# 03a_POWER-DISCRETE.net
KiCad netlist of a schematic drawn in Altium Designer
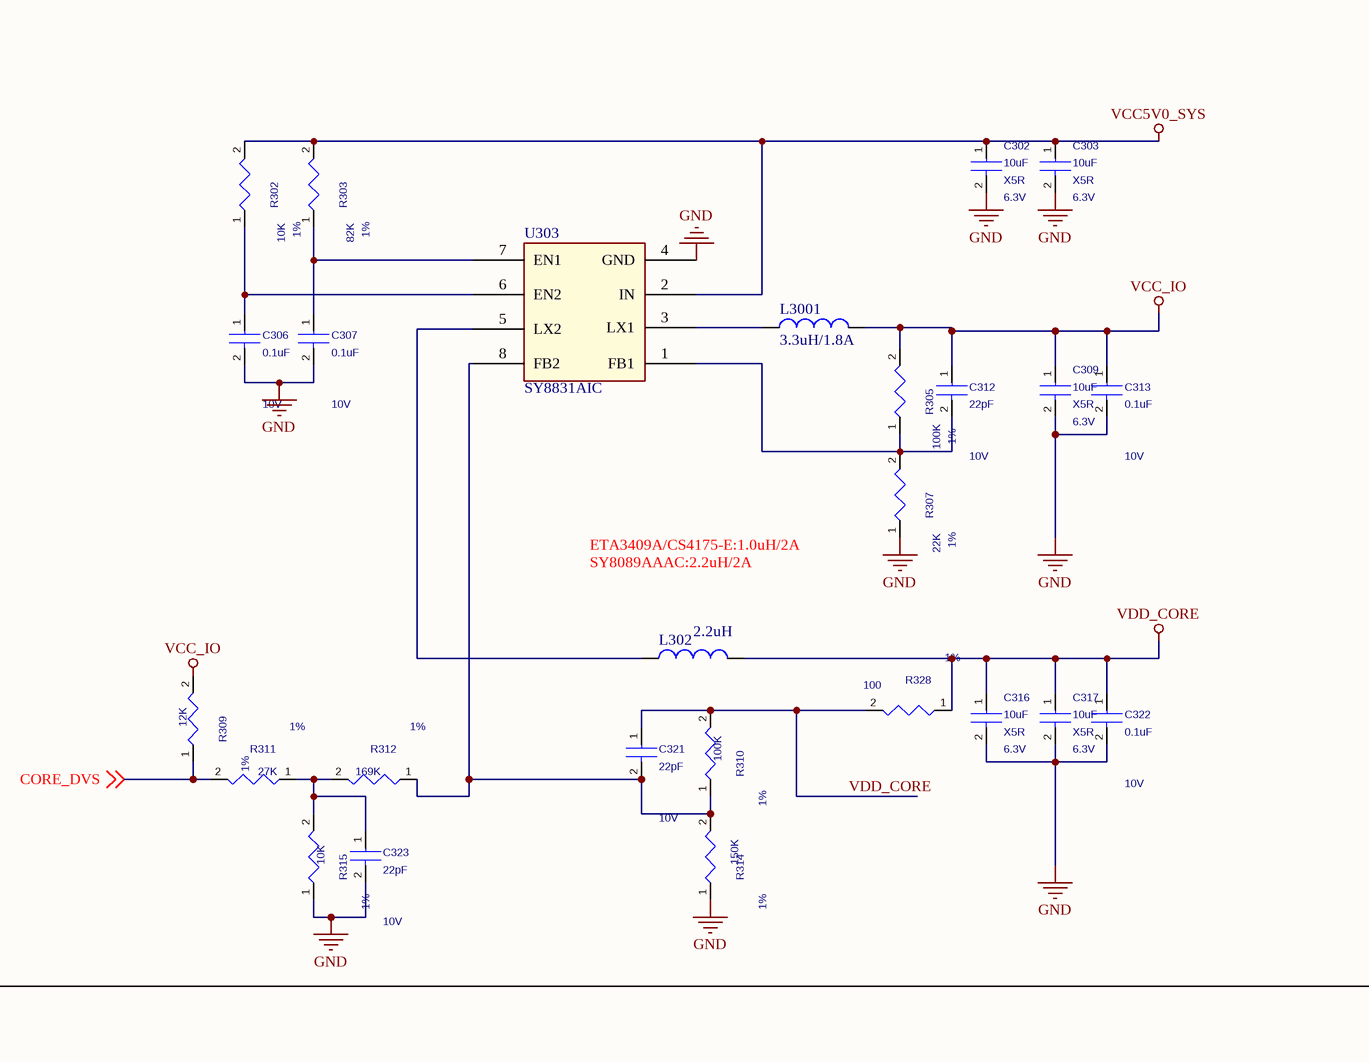
[diagram p0: 03a_POWER-DISCRETE.SchDoc, top left]
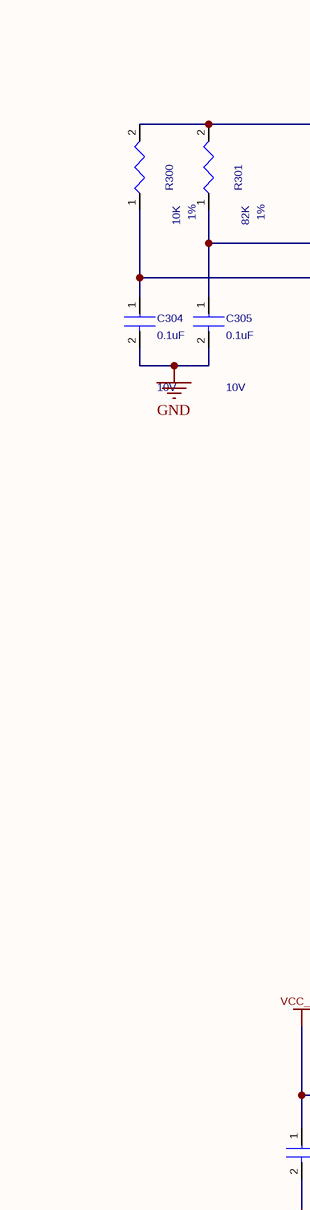
[diagram p1: 03a_POWER-DISCRETE.SchDoc, top middle]
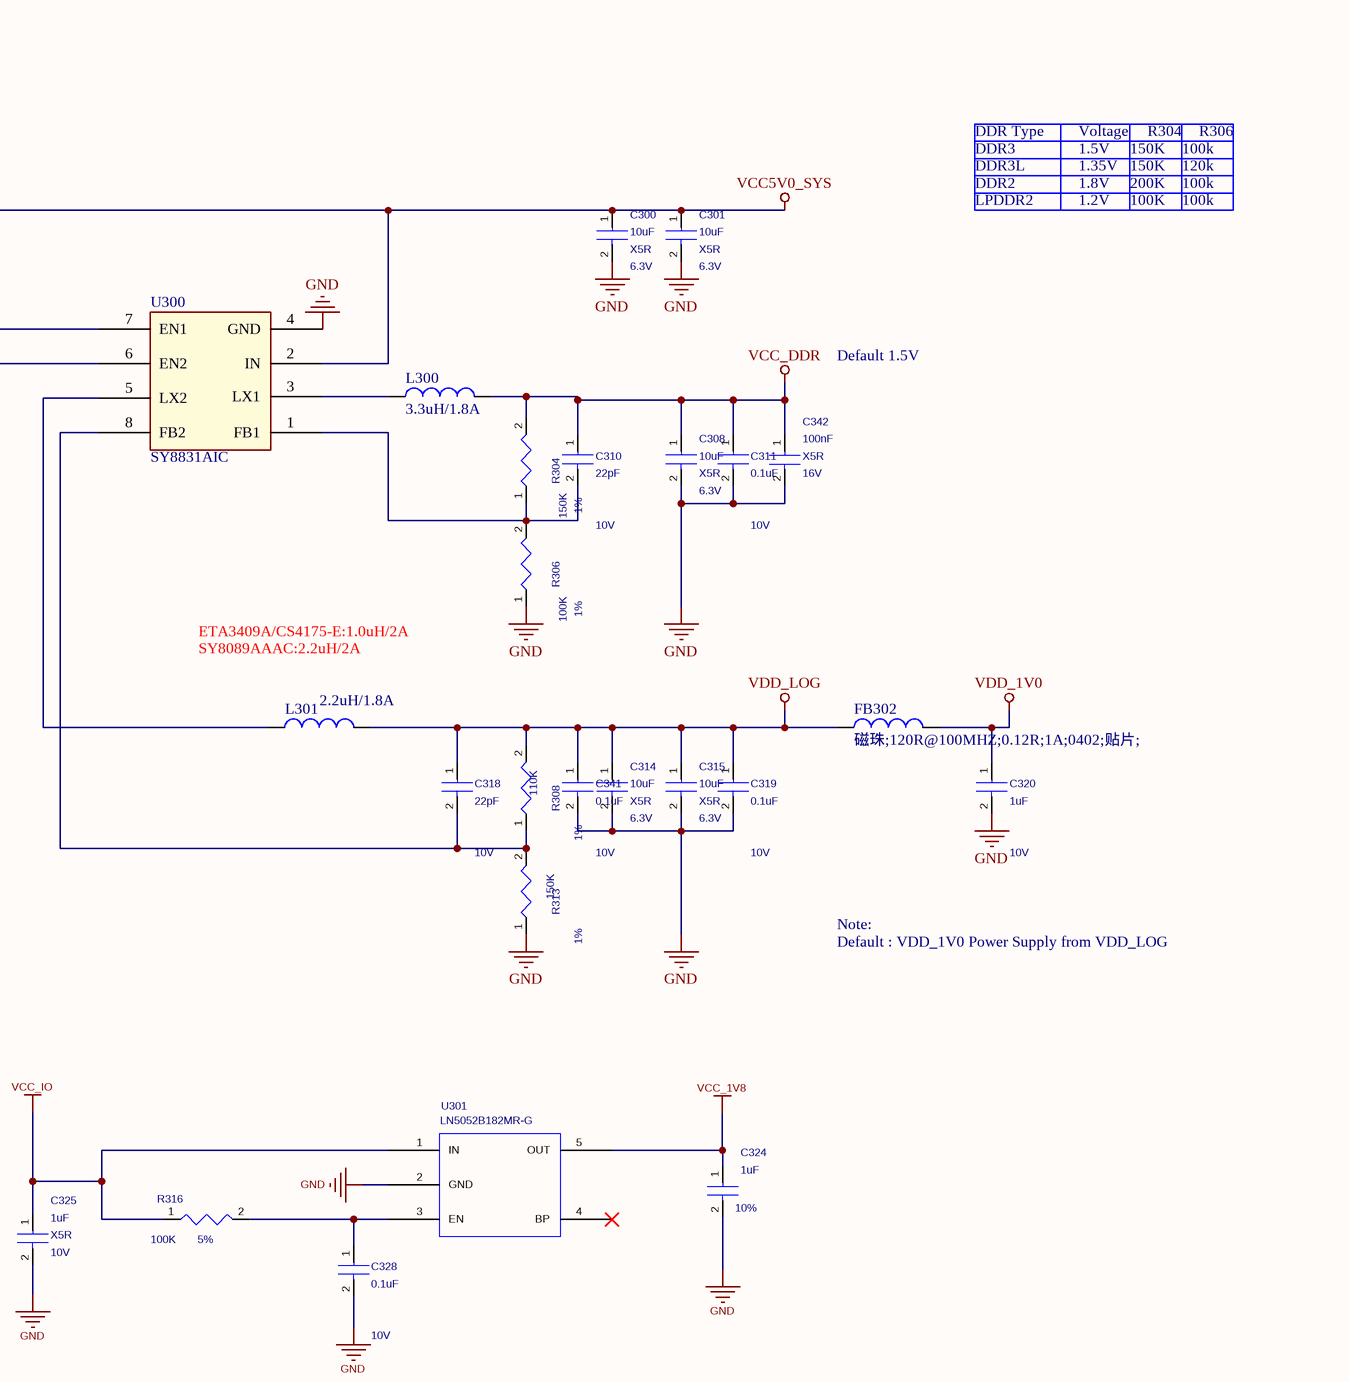
[diagram p2: 03a_POWER-DISCRETE.SchDoc, top right]
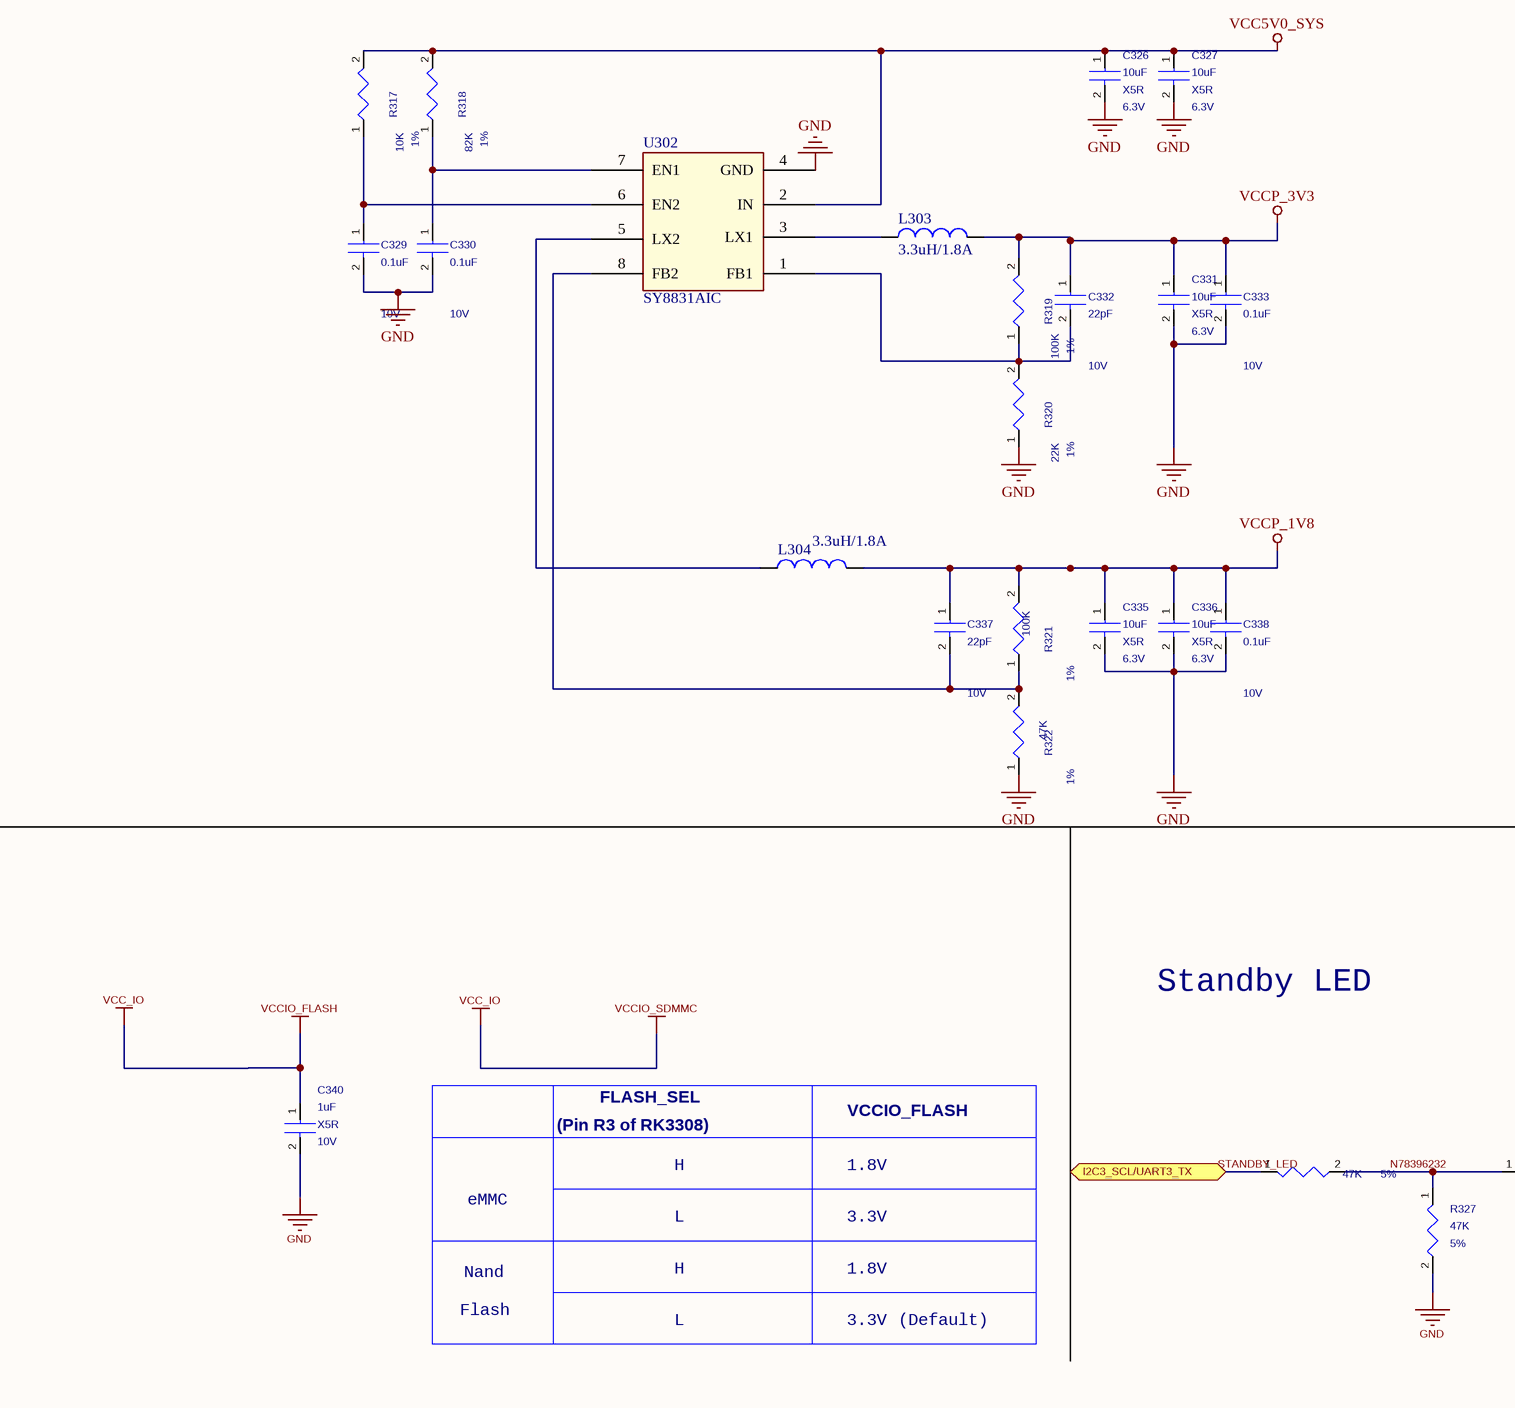
[diagram p3: 03a_POWER-DISCRETE.SchDoc, bottom left]
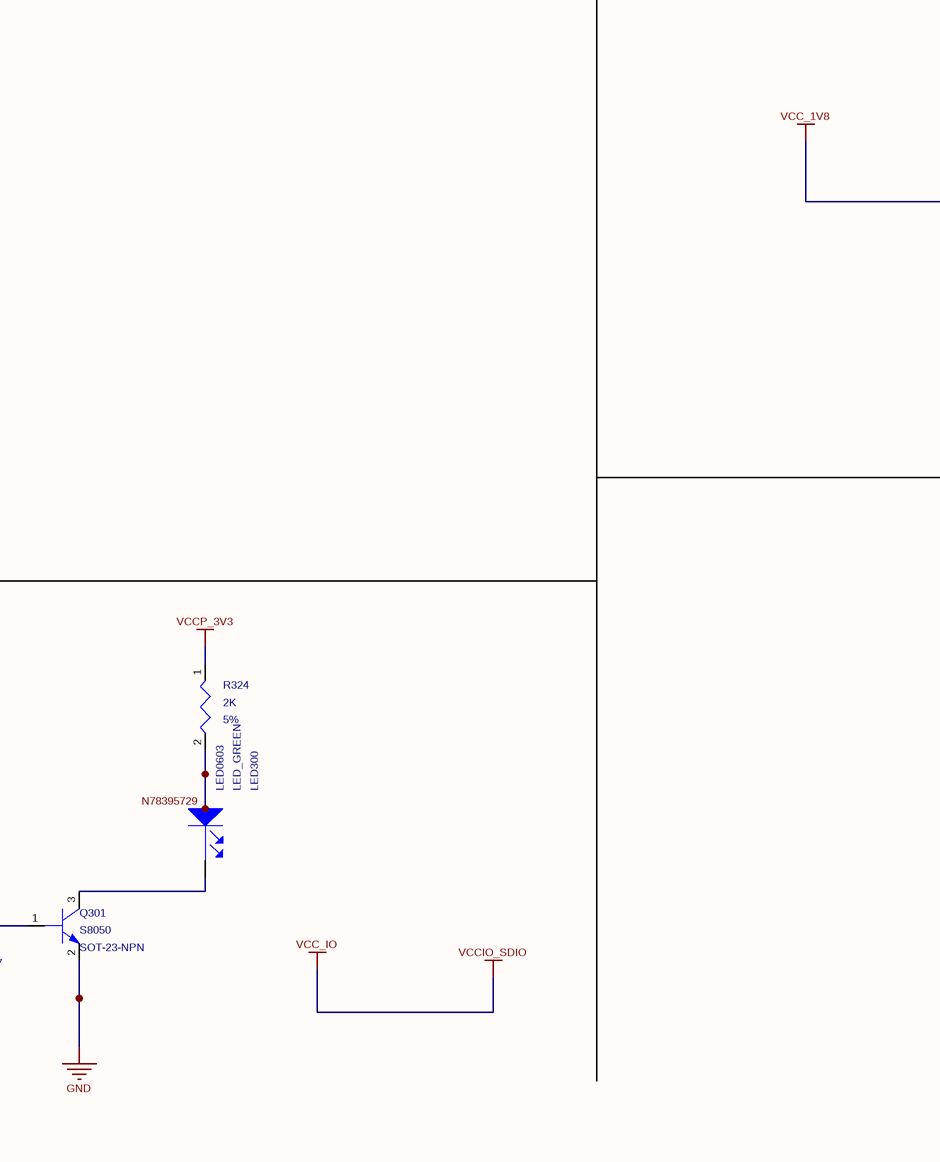
[diagram p4: 03a_POWER-DISCRETE.SchDoc, bottom middle]
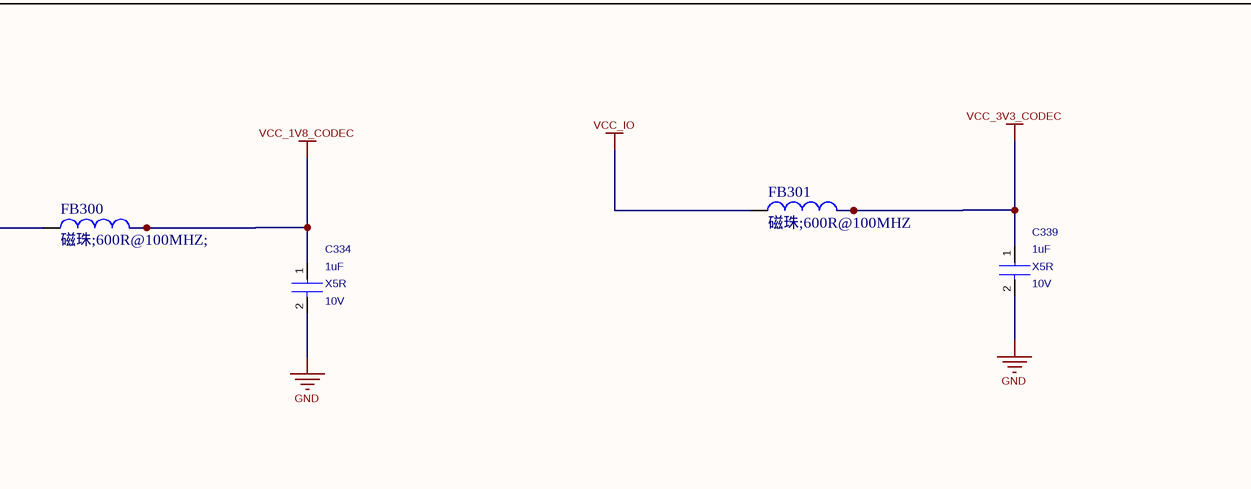
[diagram p5: 03a_POWER-DISCRETE.SchDoc, bottom right]

(export (version "E")
  (design (tool "Eeschema 10.0.6"))
  (components
    (comp (ref "C300")
      (value "10uF")
      (footprint "C0603")
      (description "cap,10.00uF,+/-10%,6.3V,X5R,C0603")
      (fields
        (field (name "DIELECTRIC") "X5R")
        (field (name "VOLTAGE") "6.3V")
        (field (name "TOLERANCE") "10%")
        (field (name "MANUFACTURER") "TDK")
      )
      (libsource (lib "*") (part "CAP_NP_2"))
    )
    (comp (ref "C301")
      (value "10uF")
      (footprint "C0603")
      (description "cap,10.00uF,+/-10%,6.3V,X5R,C0603")
      (fields
        (field (name "DIELECTRIC") "X5R")
        (field (name "VOLTAGE") "6.3V")
        (field (name "TOLERANCE") "10%")
        (field (name "MANUFACTURER") "TDK")
      )
      (libsource (lib "*") (part "CAP_NP_2"))
    )
    (comp (ref "C302")
      (value "10uF")
      (footprint "C0603")
      (description "cap,10.00uF,+/-10%,6.3V,X5R,C0603")
      (fields
        (field (name "DIELECTRIC") "X5R")
        (field (name "VOLTAGE") "6.3V")
        (field (name "TOLERANCE") "10%")
        (field (name "MANUFACTURER") "TDK")
      )
      (libsource (lib "*") (part "CAP_NP_2"))
    )
    (comp (ref "C303")
      (value "10uF")
      (footprint "C0603")
      (description "cap,10.00uF,+/-10%,6.3V,X5R,C0603")
      (fields
        (field (name "DIELECTRIC") "X5R")
        (field (name "VOLTAGE") "6.3V")
        (field (name "TOLERANCE") "10%")
        (field (name "MANUFACTURER") "TDK")
      )
      (libsource (lib "*") (part "CAP_NP_2"))
    )
    (comp (ref "C304")
      (value "0.1uF")
      (footprint "C0402")
      (description "cap,0.1uF,+/-10%,10V,X5R,C0402")
      (fields
        (field (name "TOLERANCE") "10%")
        (field (name "MANUFACTURER") "TDK")
        (field (name "VOLTAGE") "10V")
      )
      (libsource (lib "*") (part "CAP_NP_2"))
    )
    (comp (ref "C305")
      (value "0.1uF")
      (footprint "C0402")
      (description "cap,0.1uF,+/-10%,10V,X5R,C0402")
      (fields
        (field (name "TOLERANCE") "10%")
        (field (name "MANUFACTURER") "TDK")
        (field (name "VOLTAGE") "10V")
      )
      (libsource (lib "*") (part "CAP_NP_2"))
    )
    (comp (ref "C306")
      (value "0.1uF")
      (footprint "C0402")
      (description "cap,0.1uF,+/-10%,10V,X5R,C0402")
      (fields
        (field (name "TOLERANCE") "10%")
        (field (name "MANUFACTURER") "TDK")
        (field (name "VOLTAGE") "10V")
      )
      (libsource (lib "*") (part "CAP_NP_2"))
    )
    (comp (ref "C307")
      (value "0.1uF")
      (footprint "C0402")
      (description "cap,0.1uF,+/-10%,10V,X5R,C0402")
      (fields
        (field (name "TOLERANCE") "10%")
        (field (name "MANUFACTURER") "TDK")
        (field (name "VOLTAGE") "10V")
      )
      (libsource (lib "*") (part "CAP_NP_2"))
    )
    (comp (ref "C308")
      (value "10uF")
      (footprint "C0603")
      (description "cap,10.00uF,+/-10%,6.3V,X5R,C0603")
      (fields
        (field (name "DIELECTRIC") "X5R")
        (field (name "VOLTAGE") "6.3V")
        (field (name "TOLERANCE") "10%")
        (field (name "MANUFACTURER") "TDK")
      )
      (libsource (lib "*") (part "CAP_NP_2"))
    )
    (comp (ref "C309")
      (value "10uF")
      (footprint "C0603")
      (description "cap,10.00uF,+/-10%,6.3V,X5R,C0603")
      (fields
        (field (name "DIELECTRIC") "X5R")
        (field (name "VOLTAGE") "6.3V")
        (field (name "TOLERANCE") "10%")
        (field (name "MANUFACTURER") "TDK")
      )
      (libsource (lib "*") (part "CAP_NP_2"))
    )
    (comp (ref "C310")
      (value "22pF")
      (footprint "C0402")
      (description "cap,22pF,+/-10%,10V,X5R,C0402")
      (fields
        (field (name "TOLERANCE") "10%")
        (field (name "MANUFACTURER") "TDK")
        (field (name "VOLTAGE") "10V")
      )
      (libsource (lib "*") (part "CAP_NP_2"))
    )
    (comp (ref "C311")
      (value "0.1uF")
      (footprint "C0402")
      (description "cap,0.1uF,+/-10%,10V,X5R,C0402")
      (fields
        (field (name "TOLERANCE") "10%")
        (field (name "MANUFACTURER") "TDK")
        (field (name "VOLTAGE") "10V")
      )
      (libsource (lib "*") (part "CAP_NP_2"))
    )
    (comp (ref "C312")
      (value "22pF")
      (footprint "C0402")
      (description "cap,22pF,+/-10%,10V,X5R,C0402")
      (fields
        (field (name "TOLERANCE") "10%")
        (field (name "MANUFACTURER") "TDK")
        (field (name "VOLTAGE") "10V")
      )
      (libsource (lib "*") (part "CAP_NP_2"))
    )
    (comp (ref "C313")
      (value "0.1uF")
      (footprint "C0402")
      (description "cap,0.1uF,+/-10%,10V,X5R,C0402")
      (fields
        (field (name "TOLERANCE") "10%")
        (field (name "MANUFACTURER") "TDK")
        (field (name "VOLTAGE") "10V")
      )
      (libsource (lib "*") (part "CAP_NP_2"))
    )
    (comp (ref "C314")
      (value "10uF")
      (footprint "C0603")
      (description "cap,10.00uF,+/-10%,6.3V,X5R,C0603")
      (fields
        (field (name "DIELECTRIC") "X5R")
        (field (name "VOLTAGE") "6.3V")
        (field (name "TOLERANCE") "10%")
        (field (name "MANUFACTURER") "TDK")
      )
      (libsource (lib "*") (part "CAP_NP_2"))
    )
    (comp (ref "C315")
      (value "10uF")
      (footprint "C0603")
      (description "cap,10.00uF,+/-10%,6.3V,X5R,C0603")
      (fields
        (field (name "DIELECTRIC") "X5R")
        (field (name "VOLTAGE") "6.3V")
        (field (name "TOLERANCE") "10%")
        (field (name "MANUFACTURER") "TDK")
      )
      (libsource (lib "*") (part "CAP_NP_2"))
    )
    (comp (ref "C316")
      (value "10uF")
      (footprint "C0603")
      (description "cap,10.00uF,+/-10%,6.3V,X5R,C0603")
      (fields
        (field (name "DIELECTRIC") "X5R")
        (field (name "VOLTAGE") "6.3V")
        (field (name "TOLERANCE") "10%")
        (field (name "MANUFACTURER") "TDK")
      )
      (libsource (lib "*") (part "CAP_NP_2"))
    )
    (comp (ref "C317")
      (value "10uF")
      (footprint "C0603")
      (description "cap,10.00uF,+/-10%,6.3V,X5R,C0603")
      (fields
        (field (name "DIELECTRIC") "X5R")
        (field (name "VOLTAGE") "6.3V")
        (field (name "TOLERANCE") "10%")
        (field (name "MANUFACTURER") "TDK")
      )
      (libsource (lib "*") (part "CAP_NP_2"))
    )
    (comp (ref "C318")
      (value "22pF")
      (footprint "C0402")
      (description "cap,22pF,+/-10%,10V,X5R,C0402")
      (fields
        (field (name "TOLERANCE") "10%")
        (field (name "MANUFACTURER") "TDK")
        (field (name "VOLTAGE") "10V")
      )
      (libsource (lib "*") (part "CAP_NP_2"))
    )
    (comp (ref "C319")
      (value "0.1uF")
      (footprint "C0402")
      (description "cap,0.1uF,+/-10%,10V,X5R,C0402")
      (fields
        (field (name "TOLERANCE") "10%")
        (field (name "MANUFACTURER") "TDK")
        (field (name "VOLTAGE") "10V")
      )
      (libsource (lib "*") (part "CAP_NP_2"))
    )
    (comp (ref "C320")
      (value "1uF")
      (footprint "C0402")
      (description "cap,1uF,+/-10%,10V,X5R,C0402")
      (fields
        (field (name "TOLERANCE") "10%")
        (field (name "MANUFACTURER") "TDK")
        (field (name "VOLTAGE") "10V")
      )
      (libsource (lib "*") (part "CAP_NP_2"))
    )
    (comp (ref "C321")
      (value "22pF")
      (footprint "C0402")
      (description "cap,22pF,+/-10%,10V,X5R,C0402")
      (fields
        (field (name "TOLERANCE") "10%")
        (field (name "MANUFACTURER") "TDK")
        (field (name "VOLTAGE") "10V")
      )
      (libsource (lib "*") (part "CAP_NP_2"))
    )
    (comp (ref "C322")
      (value "0.1uF")
      (footprint "C0402")
      (description "cap,0.1uF,+/-10%,10V,X5R,C0402")
      (fields
        (field (name "TOLERANCE") "10%")
        (field (name "MANUFACTURER") "TDK")
        (field (name "VOLTAGE") "10V")
      )
      (libsource (lib "*") (part "CAP_NP_2"))
    )
    (comp (ref "C323")
      (value "22pF")
      (footprint "C0402")
      (description "cap,22pF,+/-10%,10V,X5R,C0402")
      (fields
        (field (name "TOLERANCE") "10%")
        (field (name "MANUFACTURER") "TDK")
        (field (name "VOLTAGE") "10V")
      )
      (libsource (lib "*") (part "CAP_NP_2"))
    )
    (comp (ref "C324")
      (value "1uF")
      (footprint "C0402")
      (description "cap,1.00uF,+/-10%,10V,X5R,C0402")
      (fields
        (field (name "VOLTAGE") "10V")
        (field (name "MANUFACTURER") "TDK")
        (field (name "TOLERANCE") "10%")
      )
      (libsource (lib "*") (part "CAP_NP_2"))
    )
    (comp (ref "C325")
      (value "1uF")
      (footprint "C0402")
      (description "cap,1.00uF,+/-10%,10V,X5R,C0402")
      (fields
        (field (name "VOLTAGE") "10V")
        (field (name "DIELECTRIC") "X5R")
        (field (name "TOLERANCE") "10%")
        (field (name "MANUFACTURER") "TDK")
      )
      (libsource (lib "*") (part "CAP_NP_2"))
    )
    (comp (ref "C326")
      (value "10uF")
      (footprint "C0603")
      (description "cap,10.00uF,+/-10%,6.3V,X5R,C0603")
      (fields
        (field (name "DIELECTRIC") "X5R")
        (field (name "VOLTAGE") "6.3V")
        (field (name "TOLERANCE") "10%")
        (field (name "MANUFACTURER") "TDK")
      )
      (libsource (lib "*") (part "CAP_NP_2"))
    )
    (comp (ref "C327")
      (value "10uF")
      (footprint "C0603")
      (description "cap,10.00uF,+/-10%,6.3V,X5R,C0603")
      (fields
        (field (name "DIELECTRIC") "X5R")
        (field (name "VOLTAGE") "6.3V")
        (field (name "TOLERANCE") "10%")
        (field (name "MANUFACTURER") "TDK")
      )
      (libsource (lib "*") (part "CAP_NP_2"))
    )
    (comp (ref "C328")
      (value "0.1uF")
      (footprint "C0402")
      (description "cap,0.1uF,+/-10%,10V,X5R,C0402")
      (fields
        (field (name "TOLERANCE") "10%")
        (field (name "MANUFACTURER") "TDK")
        (field (name "VOLTAGE") "10V")
      )
      (libsource (lib "*") (part "CAP_NP_2"))
    )
    (comp (ref "C329")
      (value "0.1uF")
      (footprint "C0402")
      (description "cap,0.1uF,+/-10%,10V,X5R,C0402")
      (fields
        (field (name "TOLERANCE") "10%")
        (field (name "MANUFACTURER") "TDK")
        (field (name "VOLTAGE") "10V")
      )
      (libsource (lib "*") (part "CAP_NP_2"))
    )
    (comp (ref "C330")
      (value "0.1uF")
      (footprint "C0402")
      (description "cap,0.1uF,+/-10%,10V,X5R,C0402")
      (fields
        (field (name "TOLERANCE") "10%")
        (field (name "MANUFACTURER") "TDK")
        (field (name "VOLTAGE") "10V")
      )
      (libsource (lib "*") (part "CAP_NP_2"))
    )
    (comp (ref "C331")
      (value "10uF")
      (footprint "C0603")
      (description "cap,10.00uF,+/-10%,6.3V,X5R,C0603")
      (fields
        (field (name "DIELECTRIC") "X5R")
        (field (name "VOLTAGE") "6.3V")
        (field (name "TOLERANCE") "10%")
        (field (name "MANUFACTURER") "TDK")
      )
      (libsource (lib "*") (part "CAP_NP_2"))
    )
    (comp (ref "C332")
      (value "22pF")
      (footprint "C0402")
      (description "cap,22pF,+/-10%,10V,X5R,C0402")
      (fields
        (field (name "TOLERANCE") "10%")
        (field (name "MANUFACTURER") "TDK")
        (field (name "VOLTAGE") "10V")
      )
      (libsource (lib "*") (part "CAP_NP_2"))
    )
    (comp (ref "C333")
      (value "0.1uF")
      (footprint "C0402")
      (description "cap,0.1uF,+/-10%,10V,X5R,C0402")
      (fields
        (field (name "TOLERANCE") "10%")
        (field (name "MANUFACTURER") "TDK")
        (field (name "VOLTAGE") "10V")
      )
      (libsource (lib "*") (part "CAP_NP_2"))
    )
    (comp (ref "C334")
      (value "1uF")
      (footprint "C0402")
      (description "cap,1.00uF,+/-10%,10V,X5R,C0402")
      (fields
        (field (name "VOLTAGE") "10V")
        (field (name "MANUFACTURER") "TDK")
        (field (name "TOLERANCE") "10%")
        (field (name "DIELECTRIC") "X5R")
      )
      (libsource (lib "*") (part "CAP_NP_2"))
    )
    (comp (ref "C335")
      (value "10uF")
      (footprint "C0603")
      (description "cap,10.00uF,+/-10%,6.3V,X5R,C0603")
      (fields
        (field (name "DIELECTRIC") "X5R")
        (field (name "VOLTAGE") "6.3V")
        (field (name "TOLERANCE") "10%")
        (field (name "MANUFACTURER") "TDK")
      )
      (libsource (lib "*") (part "CAP_NP_2"))
    )
    (comp (ref "C336")
      (value "10uF")
      (footprint "C0603")
      (description "cap,10.00uF,+/-10%,6.3V,X5R,C0603")
      (fields
        (field (name "DIELECTRIC") "X5R")
        (field (name "VOLTAGE") "6.3V")
        (field (name "TOLERANCE") "10%")
        (field (name "MANUFACTURER") "TDK")
      )
      (libsource (lib "*") (part "CAP_NP_2"))
    )
    (comp (ref "C337")
      (value "22pF")
      (footprint "C0402")
      (description "cap,22pF,+/-10%,10V,X5R,C0402")
      (fields
        (field (name "TOLERANCE") "10%")
        (field (name "MANUFACTURER") "TDK")
        (field (name "VOLTAGE") "10V")
      )
      (libsource (lib "*") (part "CAP_NP_2"))
    )
    (comp (ref "C338")
      (value "0.1uF")
      (footprint "C0402")
      (description "cap,0.1uF,+/-10%,10V,X5R,C0402")
      (fields
        (field (name "TOLERANCE") "10%")
        (field (name "MANUFACTURER") "TDK")
        (field (name "VOLTAGE") "10V")
      )
      (libsource (lib "*") (part "CAP_NP_2"))
    )
    (comp (ref "C339")
      (value "1uF")
      (footprint "C0402")
      (description "cap,1.00uF,+/-10%,10V,X5R,C0402")
      (fields
        (field (name "VOLTAGE") "10V")
        (field (name "MANUFACTURER") "TDK")
        (field (name "TOLERANCE") "10%")
        (field (name "DIELECTRIC") "X5R")
      )
      (libsource (lib "*") (part "CAP_NP_2"))
    )
    (comp (ref "C340")
      (value "1uF")
      (footprint "C0402")
      (description "cap,1.00uF,+/-10%,10V,X5R,C0402")
      (fields
        (field (name "VOLTAGE") "10V")
        (field (name "MANUFACTURER") "TDK")
        (field (name "TOLERANCE") "10%")
        (field (name "DIELECTRIC") "X5R")
      )
      (libsource (lib "*") (part "CAP_NP_2"))
    )
    (comp (ref "C341")
      (value "0.1uF")
      (footprint "C0402")
      (description "cap,0.1uF,+/-10%,10V,X5R,C0402")
      (fields
        (field (name "TOLERANCE") "10%")
        (field (name "MANUFACTURER") "TDK")
        (field (name "VOLTAGE") "10V")
      )
      (libsource (lib "*") (part "CAP_NP_2"))
    )
    (comp (ref "C342")
      (value "100nF")
      (footprint "C0402")
      (description "cap,100.00nF,+/-10%,16V,X5R,C0402")
      (fields
        (field (name "VOLTAGE") "16V")
        (field (name "TOLERANCE") "10%")
        (field (name "MANUFACTURER") "TDK")
        (field (name "DIELECTRIC") "X5R")
      )
      (libsource (lib "*") (part "CAP_NP_2"))
    )
    (comp (ref "FB300")
      (value "磁珠;600R@100MHZ;")
      (footprint "L0402")
      (description "GZ0603D601TF")
      (libsource (lib "amenuo") (part "INDUCTOR"))
    )
    (comp (ref "FB301")
      (value "磁珠;600R@100MHZ")
      (footprint "L0402")
      (description "L0603-0欧姆-1A")
      (libsource (lib "amenuo") (part "INDUCTOR"))
    )
    (comp (ref "FB302")
      (value "磁珠;120R@100MHZ;0.12R;1A;0402;贴片;")
      (footprint "L0402")
      (description "PZ1005U121-1R0T")
      (libsource (lib "amenuo") (part "INDUCTOR"))
    )
    (comp (ref "L300")
      (value "3.3uH/1.8A")
      (footprint "IND2520")
      (description "SWPA252012S3R3MT")
      (libsource (lib "amenuo") (part "INDUCTOR"))
    )
    (comp (ref "L301")
      (value "2.2uH/1.8A")
      (footprint "IND2520")
      (description "SPH252012H2R2MT")
      (libsource (lib "amenuo") (part "INDUCTOR"))
    )
    (comp (ref "L302")
      (value "2.2uH")
      (footprint "IND2520")
      (description "SPH252012H2R2MT")
      (libsource (lib "amenuo") (part "INDUCTOR"))
    )
    (comp (ref "L303")
      (value "3.3uH/1.8A")
      (footprint "IND2520")
      (description "SWPA252012S3R3MT")
      (libsource (lib "amenuo") (part "INDUCTOR"))
    )
    (comp (ref "L304")
      (value "3.3uH/1.8A")
      (footprint "IND2520")
      (description "SWPA252012S3R3MT")
      (libsource (lib "amenuo") (part "INDUCTOR"))
    )
    (comp (ref "L3001")
      (value "3.3uH/1.8A")
      (footprint "IND2520")
      (description "SWPA252012S3R3MT")
      (libsource (lib "amenuo") (part "INDUCTOR"))
    )
    (comp (ref "LED300")
      (value "LED_GREEN")
      (footprint "LED0603")
      (description "贴片LED灯，0603，绿色")
      (fields (field (name "PCB DECAL") "LED0603") (field (name "Comment") "LED"))
      (libsource (lib "*") (part "LED"))
    )
    (comp (ref "Q301")
      (value "S8050")
      (footprint "SOT23")
      (description "S8050,SOT23")
      (fields
        (field (name "PCB DECAL") "SOT-23-NPN")
        (field (name "MANUFACTURER") "长电")
        (field (name "Comment") "NPN")
      )
      (libsource (lib "*") (part "NPN"))
    )
    (comp (ref "R300")
      (value "10K")
      (footprint "R0402")
      (description "?用厚膜电阻,10K,+/-1%,R0402,1/16W.")
      (fields
        (field (name "MANUFACTURER") "YAGEO")
        (field (name "TOLERANCE") "1%")
        (field (name "Comment") "RESISTOR")
      )
      (libsource (lib "*") (part "RESISTOR"))
    )
    (comp (ref "R301")
      (value "82K")
      (footprint "R0402")
      (description "?用厚膜电阻,82K,+/-1%,R0402,1/16W.")
      (fields
        (field (name "MANUFACTURER") "YAGEO")
        (field (name "TOLERANCE") "1%")
        (field (name "Comment") "RESISTOR")
      )
      (libsource (lib "*") (part "RESISTOR"))
    )
    (comp (ref "R302")
      (value "10K")
      (footprint "R0402")
      (description "?用厚膜电阻,10K,+/-1%,R0402,1/16W.")
      (fields
        (field (name "MANUFACTURER") "YAGEO")
        (field (name "TOLERANCE") "1%")
        (field (name "Comment") "RESISTOR")
      )
      (libsource (lib "*") (part "RESISTOR"))
    )
    (comp (ref "R303")
      (value "82K")
      (footprint "R0402")
      (description "?用厚膜电阻,82K,+/-1%,R0402,1/16W.")
      (fields
        (field (name "MANUFACTURER") "YAGEO")
        (field (name "TOLERANCE") "1%")
        (field (name "Comment") "RESISTOR")
      )
      (libsource (lib "*") (part "RESISTOR"))
    )
    (comp (ref "R304")
      (value "150K")
      (footprint "R0402")
      (description "?用厚膜电阻,150K,+/-1%,R0402,1/16W.")
      (fields
        (field (name "MANUFACTURER") "YAGEO")
        (field (name "TOLERANCE") "1%")
        (field (name "Comment") "RESISTOR")
      )
      (libsource (lib "*") (part "RESISTOR"))
    )
    (comp (ref "R305")
      (value "100K")
      (footprint "R0402")
      (description "?用厚膜电阻,100K,+/-1%,R0402,1/16W.")
      (fields
        (field (name "MANUFACTURER") "YAGEO")
        (field (name "TOLERANCE") "1%")
        (field (name "Comment") "RESISTOR")
      )
      (libsource (lib "*") (part "RESISTOR"))
    )
    (comp (ref "R306")
      (value "100K")
      (footprint "R0402")
      (description "?用厚膜电阻,100K,+/-1%,R0402,1/16W.")
      (fields
        (field (name "MANUFACTURER") "YAGEO")
        (field (name "TOLERANCE") "1%")
        (field (name "Comment") "RESISTOR")
      )
      (libsource (lib "*") (part "RESISTOR"))
    )
    (comp (ref "R307")
      (value "22K")
      (footprint "R0402")
      (description "?用厚膜电阻,22K,+/-1%,R0402,1/16W.")
      (fields
        (field (name "MANUFACTURER") "YAGEO")
        (field (name "TOLERANCE") "1%")
        (field (name "Comment") "RESISTOR")
      )
      (libsource (lib "*") (part "RESISTOR"))
    )
    (comp (ref "R308")
      (value "110K")
      (footprint "R0402")
      (description "?用厚膜电阻,110K,+/-1%,R0402,1/16W.")
      (fields
        (field (name "MANUFACTURER") "YAGEO")
        (field (name "TOLERANCE") "1%")
        (field (name "Comment") "RESISTOR")
      )
      (libsource (lib "*") (part "RESISTOR"))
    )
    (comp (ref "R309")
      (value "12K")
      (footprint "R0402")
      (description "?用厚膜电阻,12K,+/-1%,R0402,1/16W.")
      (fields
        (field (name "MANUFACTURER") "YAGEO")
        (field (name "TOLERANCE") "1%")
        (field (name "Comment") "RESISTOR")
      )
      (libsource (lib "*") (part "RESISTOR"))
    )
    (comp (ref "R310")
      (value "100K")
      (footprint "R0402")
      (description "?用厚膜电阻,100K,+/-1%,R0402,1/16W.")
      (fields
        (field (name "MANUFACTURER") "YAGEO")
        (field (name "TOLERANCE") "1%")
        (field (name "Comment") "RESISTOR")
      )
      (libsource (lib "*") (part "RESISTOR"))
    )
    (comp (ref "R311")
      (value "27K")
      (footprint "R0402")
      (description "?用厚膜电阻,27K,+/-1%,R0402,1/16W.")
      (fields
        (field (name "MANUFACTURER") "YAGEO")
        (field (name "TOLERANCE") "1%")
        (field (name "Comment") "RESISTOR")
      )
      (libsource (lib "*") (part "RESISTOR"))
    )
    (comp (ref "R312")
      (value "169K")
      (footprint "R0402")
      (description "?用厚膜电阻,169K,+/-1%,R0402,1/16W.")
      (fields
        (field (name "MANUFACTURER") "YAGEO")
        (field (name "TOLERANCE") "1%")
        (field (name "Comment") "RESISTOR")
      )
      (libsource (lib "*") (part "RESISTOR"))
    )
    (comp (ref "R313")
      (value "150K")
      (footprint "R0402")
      (description "?用厚膜电阻,150K,+/-1%,R0402,1/16W.")
      (fields
        (field (name "MANUFACTURER") "YAGEO")
        (field (name "TOLERANCE") "1%")
        (field (name "Comment") "RESISTOR")
      )
      (libsource (lib "*") (part "RESISTOR"))
    )
    (comp (ref "R314")
      (value "150K")
      (footprint "R0402")
      (description "?用厚膜电阻,150K,+/-1%,R0402,1/16W.")
      (fields
        (field (name "MANUFACTURER") "YAGEO")
        (field (name "TOLERANCE") "1%")
        (field (name "Comment") "RESISTOR")
      )
      (libsource (lib "*") (part "RESISTOR"))
    )
    (comp (ref "R315")
      (value "10K")
      (footprint "R0402")
      (description "?用厚膜电阻,10K,+/-1%,R0402,1/16W.")
      (fields
        (field (name "MANUFACTURER") "YAGEO")
        (field (name "TOLERANCE") "1%")
        (field (name "Comment") "RESISTOR")
      )
      (libsource (lib "*") (part "RESISTOR"))
    )
    (comp (ref "R316")
      (value "100K")
      (footprint "R0402")
      (description "?用厚膜电阻,100K,+/-5%,R0402,1/16W.")
      (fields
        (field (name "TOLERANCE") "5%")
        (field (name "MANUFACTURER") "YAGEO")
        (field (name "Comment") "RESISTOR")
      )
      (libsource (lib "*") (part "RESISTOR"))
    )
    (comp (ref "R317")
      (value "10K")
      (footprint "R0402")
      (description "?用厚膜电阻,10K,+/-1%,R0402,1/16W.")
      (fields
        (field (name "MANUFACTURER") "YAGEO")
        (field (name "TOLERANCE") "1%")
        (field (name "Comment") "RESISTOR")
      )
      (libsource (lib "*") (part "RESISTOR"))
    )
    (comp (ref "R318")
      (value "82K")
      (footprint "R0402")
      (description "?用厚膜电阻,82K,+/-1%,R0402,1/16W.")
      (fields
        (field (name "MANUFACTURER") "YAGEO")
        (field (name "TOLERANCE") "1%")
        (field (name "Comment") "RESISTOR")
      )
      (libsource (lib "*") (part "RESISTOR"))
    )
    (comp (ref "R319")
      (value "100K")
      (footprint "R0402")
      (description "?用厚膜电阻,100K,+/-1%,R0402,1/16W.")
      (fields
        (field (name "MANUFACTURER") "YAGEO")
        (field (name "TOLERANCE") "1%")
        (field (name "Comment") "RESISTOR")
      )
      (libsource (lib "*") (part "RESISTOR"))
    )
    (comp (ref "R320")
      (value "22K")
      (footprint "R0402")
      (description "?用厚膜电阻,22K,+/-1%,R0402,1/16W.")
      (fields
        (field (name "MANUFACTURER") "YAGEO")
        (field (name "TOLERANCE") "1%")
        (field (name "Comment") "RESISTOR")
      )
      (libsource (lib "*") (part "RESISTOR"))
    )
    (comp (ref "R321")
      (value "100K")
      (footprint "R0402")
      (description "?用厚膜电阻,100K,+/-1%,R0402,1/16W.")
      (fields
        (field (name "MANUFACTURER") "YAGEO")
        (field (name "TOLERANCE") "1%")
        (field (name "Comment") "RESISTOR")
      )
      (libsource (lib "*") (part "RESISTOR"))
    )
    (comp (ref "R322")
      (value "47K")
      (footprint "R0402")
      (description "?用厚膜电阻,47K,+/-1%,R0402,1/16W.")
      (fields
        (field (name "MANUFACTURER") "YAGEO")
        (field (name "TOLERANCE") "1%")
        (field (name "Comment") "RESISTOR")
      )
      (libsource (lib "*") (part "RESISTOR"))
    )
    (comp (ref "R324")
      (value "2K")
      (footprint "R0402")
      (description "?用厚膜电阻,2K,+/-5%,R0402,1/16W.")
      (fields
        (field (name "TOLERANCE") "5%")
        (field (name "MANUFACTURER") "YAGEO")
        (field (name "Comment") "RESISTOR")
      )
      (libsource (lib "*") (part "RESISTOR"))
    )
    (comp (ref "R326")
      (value "47K")
      (footprint "R0402")
      (description "?用厚膜电阻,47K,+/-5%,R0402,1/16W.")
      (fields
        (field (name "MANUFACTURER") "YAGEO")
        (field (name "TOLERANCE") "5%")
        (field (name "Comment") "RESISTOR")
      )
      (libsource (lib "*") (part "RESISTOR"))
    )
    (comp (ref "R327")
      (value "47K")
      (footprint "R0402")
      (description "?用厚膜电阻,47K,+/-5%,R0402,1/16W.")
      (fields
        (field (name "TOLERANCE") "5%")
        (field (name "MANUFACTURER") "YAGEO")
        (field (name "Comment") "RESISTOR")
      )
      (libsource (lib "*") (part "RESISTOR"))
    )
    (comp (ref "R328")
      (value "100")
      (footprint "R0402")
      (description "?用厚膜电阻,100,+/-1%,R0402,1/16W.")
      (fields
        (field (name "MANUFACTURER") "YAGEO")
        (field (name "TOLERANCE") "1%")
        (field (name "Comment") "RESISTOR")
      )
      (libsource (lib "*") (part "RESISTOR"))
    )
    (comp (ref "U300")
      (value "SY8831AIC")
      (footprint "TSOT23-8")
      (description "SY8831AICSOT23-8")
      (libsource (lib "amenuo") (part "SY8831"))
    )
    (comp (ref "U301")
      (value "LN5052B182MR-G")
      (footprint "SOT_23_5")
      (description "High-PSRR 600mA LDO.Output1.8V.")
      (fields (field (name "MANUFACTURER") "Powtech(华润矽威）"))
      (libsource (lib "*") (part "LDO_PT5108"))
    )
    (comp (ref "U302")
      (value "SY8831AIC")
      (footprint "TSOT23-8")
      (description "SY8831AICSOT23-8")
      (libsource (lib "amenuo") (part "SY8831"))
    )
    (comp (ref "U303")
      (value "SY8831AIC")
      (footprint "TSOT23-8")
      (description "SY8831AICSOT23-8")
      (libsource (lib "amenuo") (part "SY8831"))
    )
  )
  (nets
    (net (code "1") (name "/I2C3_SCL{slash}UART3_TX") (class "Default")
      (node (ref "R326") (pin "1") (pinfunction "1_1") (pintype "passive"))
    )
    (net (code "3") (name "/N78396232") (class "Default")
      (node (ref "Q301") (pin "1") (pinfunction "BASE_1") (pintype "passive"))
      (node (ref "R326") (pin "2") (pinfunction "2_2") (pintype "passive"))
      (node (ref "R327") (pin "1") (pinfunction "1_1") (pintype "passive"))
    )
    (net (code "5") (name "CORE_DVS") (class "Default")
      (node (ref "R309") (pin "1") (pinfunction "1_1") (pintype "passive"))
      (node (ref "R311") (pin "2") (pinfunction "2_2") (pintype "passive"))
    )
    (net (code "6") (name "GND") (class "Default")
      (node (ref "C300") (pin "2") (pinfunction "2_2") (pintype "passive"))
      (node (ref "C301") (pin "2") (pinfunction "2_2") (pintype "passive"))
      (node (ref "C302") (pin "2") (pinfunction "2_2") (pintype "passive"))
      (node (ref "C303") (pin "2") (pinfunction "2_2") (pintype "passive"))
      (node (ref "C304") (pin "2") (pinfunction "2_2") (pintype "passive"))
      (node (ref "C305") (pin "2") (pinfunction "2_2") (pintype "passive"))
      (node (ref "C306") (pin "2") (pinfunction "2_2") (pintype "passive"))
      (node (ref "C307") (pin "2") (pinfunction "2_2") (pintype "passive"))
      (node (ref "C308") (pin "2") (pinfunction "2_2") (pintype "passive"))
      (node (ref "C309") (pin "2") (pinfunction "2_2") (pintype "passive"))
      (node (ref "C311") (pin "2") (pinfunction "2_2") (pintype "passive"))
      (node (ref "C313") (pin "2") (pinfunction "2_2") (pintype "passive"))
      (node (ref "C314") (pin "2") (pinfunction "2_2") (pintype "passive"))
      (node (ref "C315") (pin "2") (pinfunction "2_2") (pintype "passive"))
      (node (ref "C316") (pin "2") (pinfunction "2_2") (pintype "passive"))
      (node (ref "C317") (pin "2") (pinfunction "2_2") (pintype "passive"))
      (node (ref "C319") (pin "2") (pinfunction "2_2") (pintype "passive"))
      (node (ref "C320") (pin "2") (pinfunction "2_2") (pintype "passive"))
      (node (ref "C322") (pin "2") (pinfunction "2_2") (pintype "passive"))
      (node (ref "C323") (pin "2") (pinfunction "2_2") (pintype "passive"))
      (node (ref "C324") (pin "2") (pinfunction "2_2") (pintype "passive"))
      (node (ref "C325") (pin "2") (pinfunction "2_2") (pintype "passive"))
      (node (ref "C326") (pin "2") (pinfunction "2_2") (pintype "passive"))
      (node (ref "C327") (pin "2") (pinfunction "2_2") (pintype "passive"))
      (node (ref "C328") (pin "2") (pinfunction "2_2") (pintype "passive"))
      (node (ref "C329") (pin "2") (pinfunction "2_2") (pintype "passive"))
      (node (ref "C330") (pin "2") (pinfunction "2_2") (pintype "passive"))
      (node (ref "C331") (pin "2") (pinfunction "2_2") (pintype "passive"))
      (node (ref "C333") (pin "2") (pinfunction "2_2") (pintype "passive"))
      (node (ref "C334") (pin "2") (pinfunction "2_2") (pintype "passive"))
      (node (ref "C335") (pin "2") (pinfunction "2_2") (pintype "passive"))
      (node (ref "C336") (pin "2") (pinfunction "2_2") (pintype "passive"))
      (node (ref "C338") (pin "2") (pinfunction "2_2") (pintype "passive"))
      (node (ref "C339") (pin "2") (pinfunction "2_2") (pintype "passive"))
      (node (ref "C340") (pin "2") (pinfunction "2_2") (pintype "passive"))
      (node (ref "C341") (pin "2") (pinfunction "2_2") (pintype "passive"))
      (node (ref "C342") (pin "2") (pinfunction "2_2") (pintype "passive"))
      (node (ref "Q301") (pin "2") (pinfunction "EMITTER_2") (pintype "passive"))
      (node (ref "R306") (pin "1") (pinfunction "1_1") (pintype "passive"))
      (node (ref "R307") (pin "1") (pinfunction "1_1") (pintype "passive"))
      (node (ref "R313") (pin "1") (pinfunction "1_1") (pintype "passive"))
      (node (ref "R314") (pin "1") (pinfunction "1_1") (pintype "passive"))
      (node (ref "R315") (pin "1") (pinfunction "1_1") (pintype "passive"))
      (node (ref "R320") (pin "1") (pinfunction "1_1") (pintype "passive"))
      (node (ref "R322") (pin "1") (pinfunction "1_1") (pintype "passive"))
      (node (ref "R327") (pin "2") (pinfunction "2_2") (pintype "passive"))
      (node (ref "U300") (pin "4") (pinfunction "GND_4") (pintype "passive"))
      (node (ref "U301") (pin "2") (pinfunction "GND_2") (pintype "passive"))
      (node (ref "U302") (pin "4") (pinfunction "GND_4") (pintype "passive"))
      (node (ref "U303") (pin "4") (pinfunction "GND_4") (pintype "passive"))
    )
    (net (code "7") (name "Net-(C323-Pad1)") (class "Default")
      (node (ref "C323") (pin "1") (pinfunction "1_1") (pintype "passive"))
      (node (ref "R311") (pin "1") (pinfunction "1_1") (pintype "passive"))
      (node (ref "R312") (pin "2") (pinfunction "2_2") (pintype "passive"))
      (node (ref "R315") (pin "2") (pinfunction "2_2") (pintype "passive"))
    )
    (net (code "8") (name "Net-(LED300-ANODE)") (class "Default")
      (node (ref "LED300") (pin "1") (pinfunction "ANODE_1") (pintype "passive"))
      (node (ref "R324") (pin "2") (pinfunction "2_2") (pintype "passive"))
    )
    (net (code "9") (name "Net-(LED300-CATHODE)") (class "Default")
      (node (ref "LED300") (pin "2") (pinfunction "CATHODE_2") (pintype "passive"))
      (node (ref "Q301") (pin "3") (pinfunction "COLLECTOR_3") (pintype "passive"))
    )
    (net (code "10") (name "Net-(U300-EN1)") (class "Default")
      (node (ref "C305") (pin "1") (pinfunction "1_1") (pintype "passive"))
      (node (ref "R301") (pin "1") (pinfunction "1_1") (pintype "passive"))
      (node (ref "U300") (pin "7") (pinfunction "EN1_7") (pintype "passive"))
    )
    (net (code "11") (name "Net-(U300-EN2)") (class "Default")
      (node (ref "C304") (pin "1") (pinfunction "1_1") (pintype "passive"))
      (node (ref "R300") (pin "1") (pinfunction "1_1") (pintype "passive"))
      (node (ref "U300") (pin "6") (pinfunction "EN2_6") (pintype "passive"))
    )
    (net (code "12") (name "Net-(U300-FB1)") (class "Default")
      (node (ref "C310") (pin "2") (pinfunction "2_2") (pintype "passive"))
      (node (ref "R304") (pin "1") (pinfunction "1_1") (pintype "passive"))
      (node (ref "R306") (pin "2") (pinfunction "2_2") (pintype "passive"))
      (node (ref "U300") (pin "1") (pinfunction "FB1_1") (pintype "passive"))
    )
    (net (code "13") (name "Net-(U300-FB2)") (class "Default")
      (node (ref "C318") (pin "2") (pinfunction "2_2") (pintype "passive"))
      (node (ref "R308") (pin "1") (pinfunction "1_1") (pintype "passive"))
      (node (ref "R313") (pin "2") (pinfunction "2_2") (pintype "passive"))
      (node (ref "U300") (pin "8") (pinfunction "FB2_8") (pintype "passive"))
    )
    (net (code "14") (name "Net-(U300-LX1)") (class "Default")
      (node (ref "L300") (pin "1") (pinfunction "1_1") (pintype "passive"))
      (node (ref "U300") (pin "3") (pinfunction "LX1_3") (pintype "passive"))
    )
    (net (code "15") (name "Net-(U300-LX2)") (class "Default")
      (node (ref "L301") (pin "1") (pinfunction "1_1") (pintype "passive"))
      (node (ref "U300") (pin "5") (pinfunction "LX2_5") (pintype "passive"))
    )
    (net (code "16") (name "Net-(U301-EN)") (class "Default")
      (node (ref "C328") (pin "1") (pinfunction "1_1") (pintype "passive"))
      (node (ref "R316") (pin "2") (pinfunction "2_2") (pintype "passive"))
      (node (ref "U301") (pin "3") (pinfunction "EN_3") (pintype "passive"))
    )
    (net (code "17") (name "Net-(U302-EN1)") (class "Default")
      (node (ref "C330") (pin "1") (pinfunction "1_1") (pintype "passive"))
      (node (ref "R318") (pin "1") (pinfunction "1_1") (pintype "passive"))
      (node (ref "U302") (pin "7") (pinfunction "EN1_7") (pintype "passive"))
    )
    (net (code "18") (name "Net-(U302-EN2)") (class "Default")
      (node (ref "C329") (pin "1") (pinfunction "1_1") (pintype "passive"))
      (node (ref "R317") (pin "1") (pinfunction "1_1") (pintype "passive"))
      (node (ref "U302") (pin "6") (pinfunction "EN2_6") (pintype "passive"))
    )
    (net (code "19") (name "Net-(U302-FB1)") (class "Default")
      (node (ref "C332") (pin "2") (pinfunction "2_2") (pintype "passive"))
      (node (ref "R319") (pin "1") (pinfunction "1_1") (pintype "passive"))
      (node (ref "R320") (pin "2") (pinfunction "2_2") (pintype "passive"))
      (node (ref "U302") (pin "1") (pinfunction "FB1_1") (pintype "passive"))
    )
    (net (code "20") (name "Net-(U302-FB2)") (class "Default")
      (node (ref "C337") (pin "2") (pinfunction "2_2") (pintype "passive"))
      (node (ref "R321") (pin "1") (pinfunction "1_1") (pintype "passive"))
      (node (ref "R322") (pin "2") (pinfunction "2_2") (pintype "passive"))
      (node (ref "U302") (pin "8") (pinfunction "FB2_8") (pintype "passive"))
    )
    (net (code "21") (name "Net-(U302-LX1)") (class "Default")
      (node (ref "L303") (pin "1") (pinfunction "1_1") (pintype "passive"))
      (node (ref "U302") (pin "3") (pinfunction "LX1_3") (pintype "passive"))
    )
    (net (code "22") (name "Net-(U302-LX2)") (class "Default")
      (node (ref "L304") (pin "1") (pinfunction "1_1") (pintype "passive"))
      (node (ref "U302") (pin "5") (pinfunction "LX2_5") (pintype "passive"))
    )
    (net (code "23") (name "Net-(U303-EN1)") (class "Default")
      (node (ref "C307") (pin "1") (pinfunction "1_1") (pintype "passive"))
      (node (ref "R303") (pin "1") (pinfunction "1_1") (pintype "passive"))
      (node (ref "U303") (pin "7") (pinfunction "EN1_7") (pintype "passive"))
    )
    (net (code "24") (name "Net-(U303-EN2)") (class "Default")
      (node (ref "C306") (pin "1") (pinfunction "1_1") (pintype "passive"))
      (node (ref "R302") (pin "1") (pinfunction "1_1") (pintype "passive"))
      (node (ref "U303") (pin "6") (pinfunction "EN2_6") (pintype "passive"))
    )
    (net (code "25") (name "Net-(U303-FB1)") (class "Default")
      (node (ref "C312") (pin "2") (pinfunction "2_2") (pintype "passive"))
      (node (ref "R305") (pin "1") (pinfunction "1_1") (pintype "passive"))
      (node (ref "R307") (pin "2") (pinfunction "2_2") (pintype "passive"))
      (node (ref "U303") (pin "1") (pinfunction "FB1_1") (pintype "passive"))
    )
    (net (code "26") (name "Net-(U303-FB2)") (class "Default")
      (node (ref "C321") (pin "2") (pinfunction "2_2") (pintype "passive"))
      (node (ref "R310") (pin "1") (pinfunction "1_1") (pintype "passive"))
      (node (ref "R312") (pin "1") (pinfunction "1_1") (pintype "passive"))
      (node (ref "R314") (pin "2") (pinfunction "2_2") (pintype "passive"))
      (node (ref "U303") (pin "8") (pinfunction "FB2_8") (pintype "passive"))
    )
    (net (code "27") (name "Net-(U303-LX1)") (class "Default")
      (node (ref "L3001") (pin "1") (pinfunction "1_1") (pintype "passive"))
      (node (ref "U303") (pin "3") (pinfunction "LX1_3") (pintype "passive"))
    )
    (net (code "28") (name "Net-(U303-LX2)") (class "Default")
      (node (ref "L302") (pin "1") (pinfunction "1_1") (pintype "passive"))
      (node (ref "U303") (pin "5") (pinfunction "LX2_5") (pintype "passive"))
    )
    (net (code "29") (name "VCC5V0_SYS") (class "Default")
      (node (ref "C300") (pin "1") (pinfunction "1_1") (pintype "passive"))
      (node (ref "C301") (pin "1") (pinfunction "1_1") (pintype "passive"))
      (node (ref "C302") (pin "1") (pinfunction "1_1") (pintype "passive"))
      (node (ref "C303") (pin "1") (pinfunction "1_1") (pintype "passive"))
      (node (ref "C326") (pin "1") (pinfunction "1_1") (pintype "passive"))
      (node (ref "C327") (pin "1") (pinfunction "1_1") (pintype "passive"))
      (node (ref "R300") (pin "2") (pinfunction "2_2") (pintype "passive"))
      (node (ref "R301") (pin "2") (pinfunction "2_2") (pintype "passive"))
      (node (ref "R302") (pin "2") (pinfunction "2_2") (pintype "passive"))
      (node (ref "R303") (pin "2") (pinfunction "2_2") (pintype "passive"))
      (node (ref "R317") (pin "2") (pinfunction "2_2") (pintype "passive"))
      (node (ref "R318") (pin "2") (pinfunction "2_2") (pintype "passive"))
      (node (ref "U300") (pin "2") (pinfunction "IN_2") (pintype "passive"))
      (node (ref "U302") (pin "2") (pinfunction "IN_2") (pintype "passive"))
      (node (ref "U303") (pin "2") (pinfunction "IN_2") (pintype "passive"))
    )
    (net (code "30") (name "VCCIO_FLASH") (class "Default")
      (node (ref "C309") (pin "1") (pinfunction "1_1") (pintype "passive"))
      (node (ref "C312") (pin "1") (pinfunction "1_1") (pintype "passive"))
      (node (ref "C313") (pin "1") (pinfunction "1_1") (pintype "passive"))
      (node (ref "C325") (pin "1") (pinfunction "1_1") (pintype "passive"))
      (node (ref "C340") (pin "1") (pinfunction "1_1") (pintype "passive"))
      (node (ref "FB301") (pin "1") (pinfunction "1_1") (pintype "passive"))
      (node (ref "L3001") (pin "2") (pinfunction "2_2") (pintype "passive"))
      (node (ref "R305") (pin "2") (pinfunction "2_2") (pintype "passive"))
      (node (ref "R309") (pin "2") (pinfunction "2_2") (pintype "passive"))
      (node (ref "R316") (pin "1") (pinfunction "1_1") (pintype "passive"))
      (node (ref "U301") (pin "1") (pinfunction "IN_1") (pintype "passive"))
    )
    (net (code "31") (name "VCCP_1V8") (class "Default")
      (node (ref "C335") (pin "1") (pinfunction "1_1") (pintype "passive"))
      (node (ref "C336") (pin "1") (pinfunction "1_1") (pintype "passive"))
      (node (ref "C337") (pin "1") (pinfunction "1_1") (pintype "passive"))
      (node (ref "C338") (pin "1") (pinfunction "1_1") (pintype "passive"))
      (node (ref "L304") (pin "2") (pinfunction "2_2") (pintype "passive"))
      (node (ref "R321") (pin "2") (pinfunction "2_2") (pintype "passive"))
    )
    (net (code "32") (name "VCCP_3V3") (class "Default")
      (node (ref "C331") (pin "1") (pinfunction "1_1") (pintype "passive"))
      (node (ref "C332") (pin "1") (pinfunction "1_1") (pintype "passive"))
      (node (ref "C333") (pin "1") (pinfunction "1_1") (pintype "passive"))
      (node (ref "L303") (pin "2") (pinfunction "2_2") (pintype "passive"))
      (node (ref "R319") (pin "2") (pinfunction "2_2") (pintype "passive"))
      (node (ref "R324") (pin "1") (pinfunction "1_1") (pintype "passive"))
    )
    (net (code "33") (name "VCC_1V8") (class "Default")
      (node (ref "C324") (pin "1") (pinfunction "1_1") (pintype "passive"))
      (node (ref "FB300") (pin "1") (pinfunction "1_1") (pintype "passive"))
      (node (ref "U301") (pin "5") (pinfunction "OUT_5") (pintype "passive"))
    )
    (net (code "34") (name "VCC_1V8_CODEC") (class "Default")
      (node (ref "C334") (pin "1") (pinfunction "1_1") (pintype "passive"))
      (node (ref "FB300") (pin "2") (pinfunction "2_2") (pintype "passive"))
    )
    (net (code "35") (name "VCC_3V3_CODEC") (class "Default")
      (node (ref "C339") (pin "1") (pinfunction "1_1") (pintype "passive"))
      (node (ref "FB301") (pin "2") (pinfunction "2_2") (pintype "passive"))
    )
    (net (code "36") (name "VCC_DDR") (class "Default")
      (node (ref "C308") (pin "1") (pinfunction "1_1") (pintype "passive"))
      (node (ref "C310") (pin "1") (pinfunction "1_1") (pintype "passive"))
      (node (ref "C311") (pin "1") (pinfunction "1_1") (pintype "passive"))
      (node (ref "C342") (pin "1") (pinfunction "1_1") (pintype "passive"))
      (node (ref "L300") (pin "2") (pinfunction "2_2") (pintype "passive"))
      (node (ref "R304") (pin "2") (pinfunction "2_2") (pintype "passive"))
    )
    (net (code "37") (name "VDD_1V0") (class "Default")
      (node (ref "C320") (pin "1") (pinfunction "1_1") (pintype "passive"))
      (node (ref "FB302") (pin "2") (pinfunction "2_2") (pintype "passive"))
    )
    (net (code "38") (name "VDD_CORE") (class "Default")
      (node (ref "C316") (pin "1") (pinfunction "1_1") (pintype "passive"))
      (node (ref "C317") (pin "1") (pinfunction "1_1") (pintype "passive"))
      (node (ref "C321") (pin "1") (pinfunction "1_1") (pintype "passive"))
      (node (ref "C322") (pin "1") (pinfunction "1_1") (pintype "passive"))
      (node (ref "L302") (pin "2") (pinfunction "2_2") (pintype "passive"))
      (node (ref "R310") (pin "2") (pinfunction "2_2") (pintype "passive"))
      (node (ref "R328") (pin "1") (pinfunction "1_1") (pintype "passive"))
      (node (ref "R328") (pin "2") (pinfunction "2_2") (pintype "passive"))
    )
    (net (code "39") (name "VDD_LOG") (class "Default")
      (node (ref "C314") (pin "1") (pinfunction "1_1") (pintype "passive"))
      (node (ref "C315") (pin "1") (pinfunction "1_1") (pintype "passive"))
      (node (ref "C318") (pin "1") (pinfunction "1_1") (pintype "passive"))
      (node (ref "C319") (pin "1") (pinfunction "1_1") (pintype "passive"))
      (node (ref "C341") (pin "1") (pinfunction "1_1") (pintype "passive"))
      (node (ref "FB302") (pin "1") (pinfunction "1_1") (pintype "passive"))
      (node (ref "L301") (pin "2") (pinfunction "2_2") (pintype "passive"))
      (node (ref "R308") (pin "2") (pinfunction "2_2") (pintype "passive"))
    )
    (net (code "40") (name "unconnected-(U301-BP-Pad4)") (class "Default")
      (node (ref "U301") (pin "4") (pinfunction "BP_4") (pintype "passive+no_connect"))
    )
  )
)
